# ArachnoProto.net
KiCad netlist of a schematic drawn in EAGLE
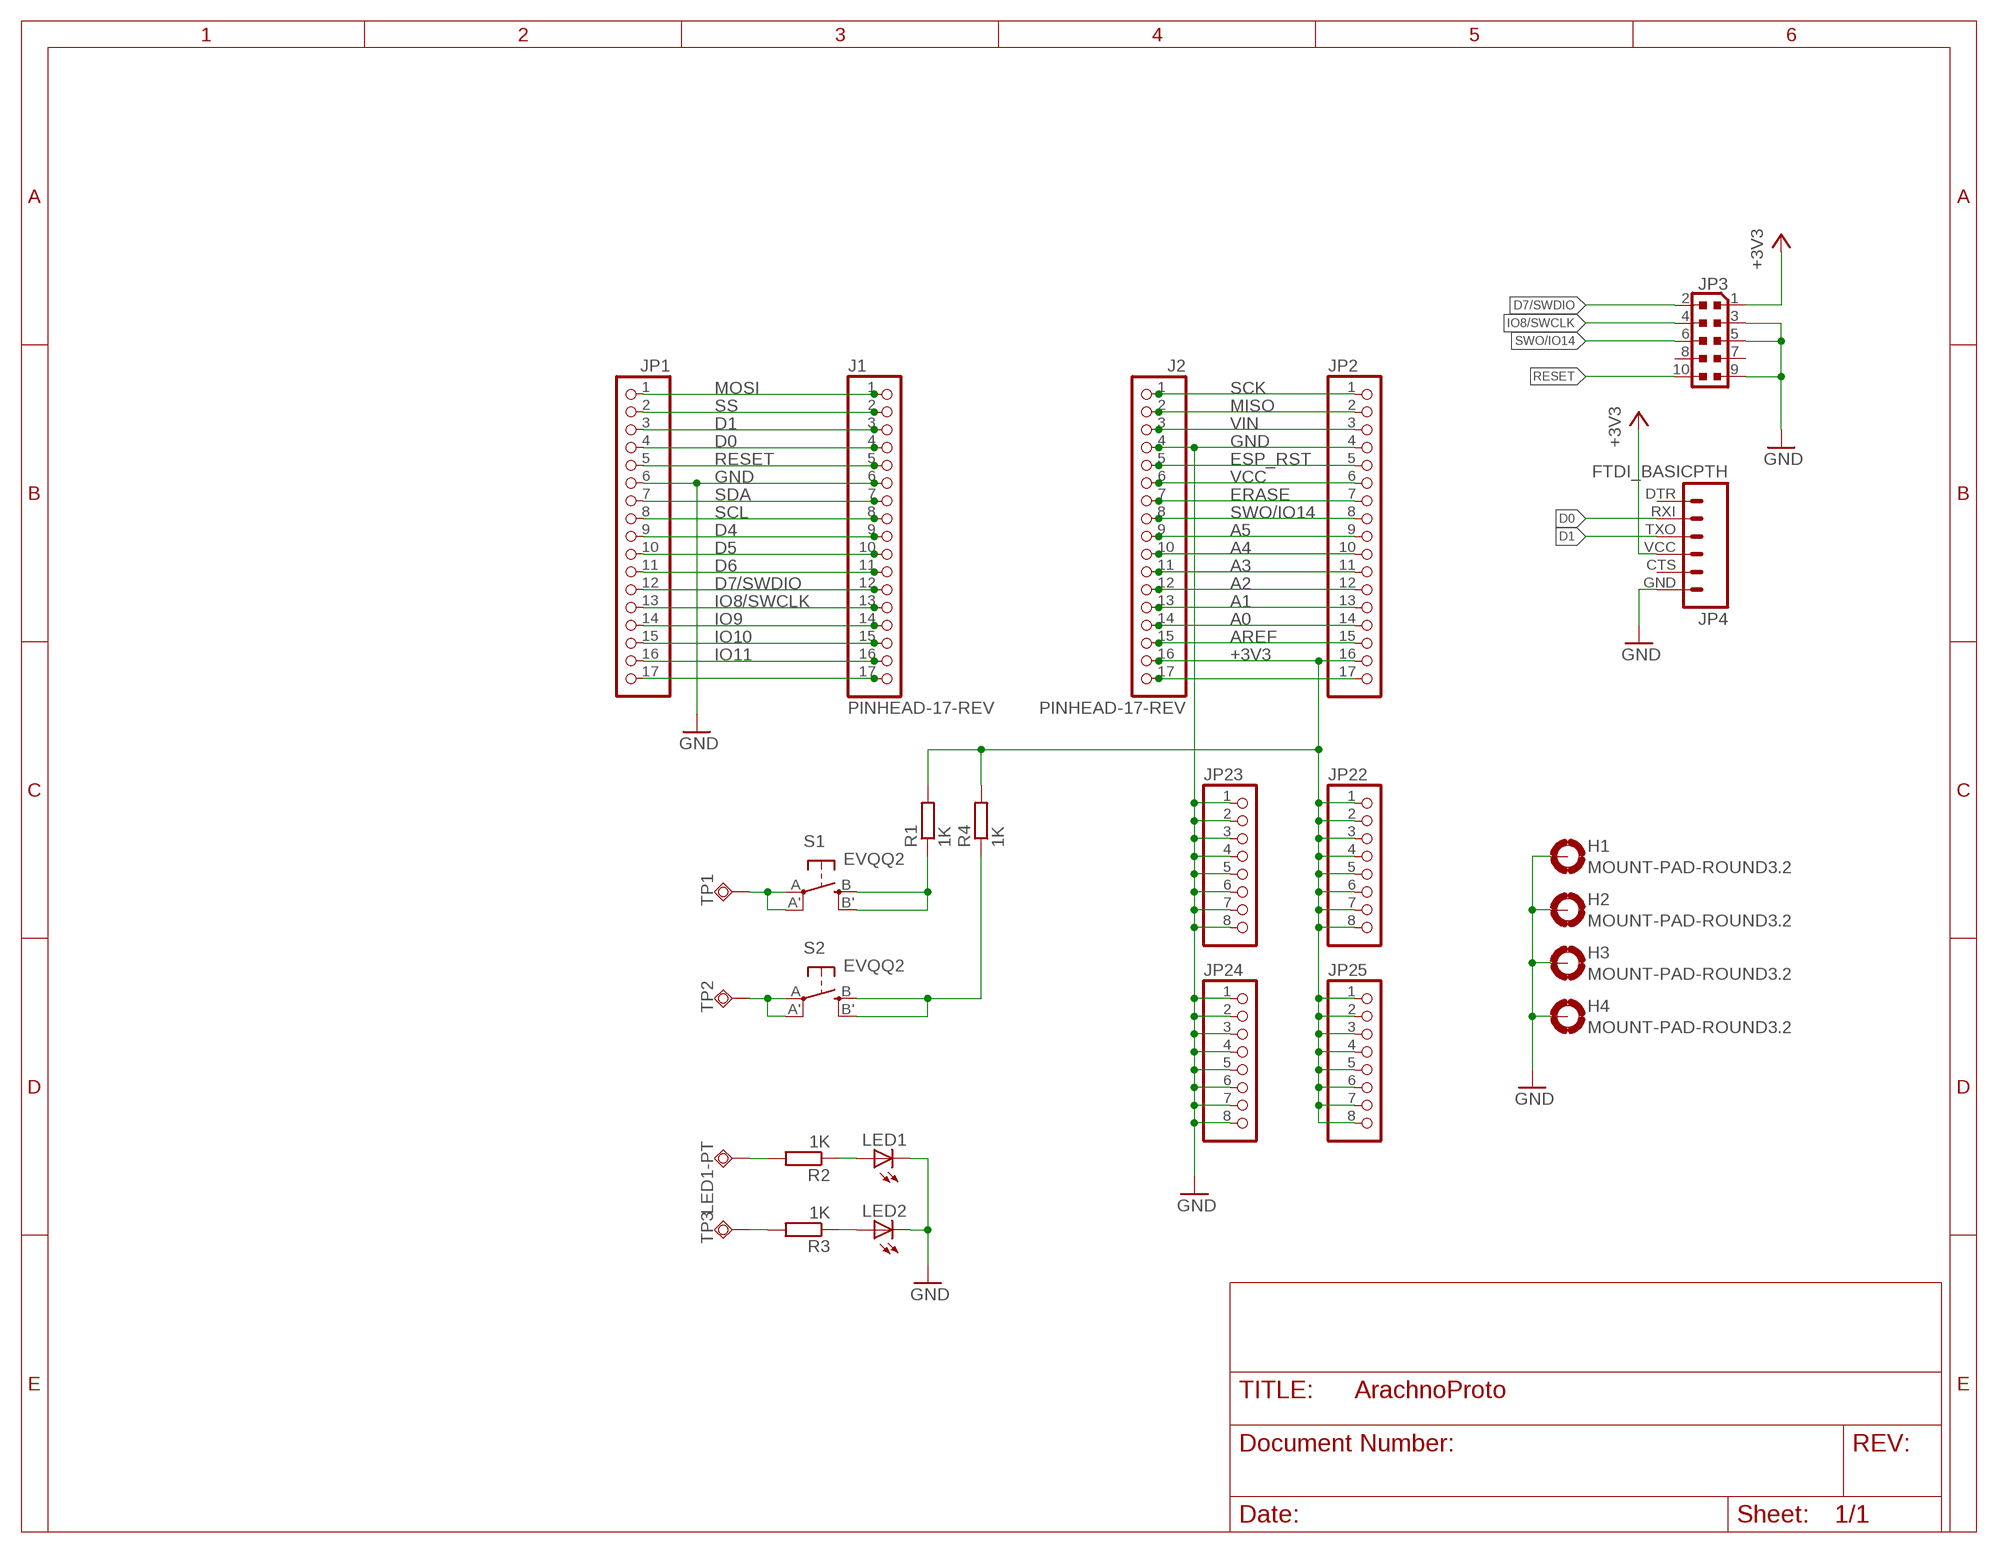
[diagram p0: schematic, sheet 1]

(export (version "E")
  (design (tool "Eeschema 10.0.6"))
  (components
    (comp (ref "H1")
      (value "MOUNT-PAD-ROUND3.2")
      (footprint "eagle-import:3,2-PAD")
      (libsource (lib "eagle-import") (part "MOUNT-PAD-ROUND3.2"))
    )
    (comp (ref "H2")
      (value "MOUNT-PAD-ROUND3.2")
      (footprint "eagle-import:3,2-PAD")
      (libsource (lib "eagle-import") (part "MOUNT-PAD-ROUND3.2"))
    )
    (comp (ref "H3")
      (value "MOUNT-PAD-ROUND3.2")
      (footprint "eagle-import:3,2-PAD")
      (libsource (lib "eagle-import") (part "MOUNT-PAD-ROUND3.2"))
    )
    (comp (ref "H4")
      (value "MOUNT-PAD-ROUND3.2")
      (footprint "eagle-import:3,2-PAD")
      (libsource (lib "eagle-import") (part "MOUNT-PAD-ROUND3.2"))
    )
    (comp (ref "J1")
      (value "PINHEAD-17-REV")
      (footprint "eagle-import:4UCONN-12573")
      (libsource (lib "eagle-import") (part "PINHEAD-17-REV"))
    )
    (comp (ref "J2")
      (value "PINHEAD-17-REV")
      (footprint "eagle-import:4UCONN-12573")
      (libsource (lib "eagle-import") (part "PINHEAD-17-REV"))
    )
    (comp (ref "JP1")
      (value "PINHD-1X17")
      (footprint "eagle-import:1X17")
      (libsource (lib "eagle-import") (part "PINHD-1X17"))
    )
    (comp (ref "JP2")
      (value "PINHD-1X17")
      (footprint "eagle-import:1X17")
      (libsource (lib "eagle-import") (part "PINHD-1X17"))
    )
    (comp (ref "JP3")
      (value "PINHEAD_PINHD-2X5PASSO127")
      (footprint "eagle-import:PINHEAD_2X05_127")
      (libsource (lib "eagle-import") (part "PINHEAD_PINHD-2X5PASSO127"))
    )
    (comp (ref "JP4")
      (value "FTDI_BASICPTH")
      (footprint "eagle-import:FTDI_BASIC")
      (libsource (lib "eagle-import") (part "FTDI_BASICPTH"))
    )
    (comp (ref "JP22")
      (value "PINHD-1X8")
      (footprint "eagle-import:1X08")
      (libsource (lib "eagle-import") (part "PINHD-1X8"))
    )
    (comp (ref "JP23")
      (value "PINHD-1X8")
      (footprint "eagle-import:1X08")
      (libsource (lib "eagle-import") (part "PINHD-1X8"))
    )
    (comp (ref "JP24")
      (value "PINHD-1X8")
      (footprint "eagle-import:1X08")
      (libsource (lib "eagle-import") (part "PINHD-1X8"))
    )
    (comp (ref "JP25")
      (value "PINHD-1X8")
      (footprint "eagle-import:1X08")
      (libsource (lib "eagle-import") (part "PINHD-1X8"))
    )
    (comp (ref "LED1")
      (value "LEDCHIPLED_1206")
      (footprint "eagle-import:CHIPLED_1206")
      (libsource (lib "eagle-import") (part "LEDCHIPLED_1206"))
    )
    (comp (ref "LED1-PT")
      (value "TPSQPAD1-20Y")
      (footprint "eagle-import:P1-20Y")
      (libsource (lib "eagle-import") (part "TPSQPAD1-20Y"))
    )
    (comp (ref "LED2")
      (value "LEDCHIPLED_1206")
      (footprint "eagle-import:CHIPLED_1206")
      (libsource (lib "eagle-import") (part "LEDCHIPLED_1206"))
    )
    (comp (ref "R1")
      (value "1K")
      (footprint "eagle-import:R1206")
      (libsource (lib "eagle-import") (part "R-EU_R1206"))
    )
    (comp (ref "R2")
      (value "1K")
      (footprint "eagle-import:R1206")
      (libsource (lib "eagle-import") (part "R-EU_R1206"))
    )
    (comp (ref "R3")
      (value "1K")
      (footprint "eagle-import:R1206")
      (libsource (lib "eagle-import") (part "R-EU_R1206"))
    )
    (comp (ref "R4")
      (value "1K")
      (footprint "eagle-import:R1206")
      (libsource (lib "eagle-import") (part "R-EU_R1206"))
    )
    (comp (ref "S1")
      (value "EVQQ2")
      (footprint "eagle-import:EVQ-Q2")
      (libsource (lib "eagle-import") (part "EVQQ2"))
    )
    (comp (ref "S2")
      (value "EVQQ2")
      (footprint "eagle-import:EVQ-Q2")
      (libsource (lib "eagle-import") (part "EVQQ2"))
    )
    (comp (ref "TP1")
      (value "TPSQPAD1-20Y")
      (footprint "eagle-import:P1-20Y")
      (libsource (lib "eagle-import") (part "TPSQPAD1-20Y"))
    )
    (comp (ref "TP2")
      (value "TPSQPAD1-20Y")
      (footprint "eagle-import:P1-20Y")
      (libsource (lib "eagle-import") (part "TPSQPAD1-20Y"))
    )
    (comp (ref "TP3")
      (value "TPSQPAD1-20Y")
      (footprint "eagle-import:P1-20Y")
      (libsource (lib "eagle-import") (part "TPSQPAD1-20Y"))
    )
  )
  (nets
    (net (code "1") (name "+3V3") (class "Default")
      (node (ref "J2") (pin "16") (pinfunction "16_16") (pintype "passive"))
      (node (ref "J2") (pin "33") (pinfunction "33_33") (pintype "passive"))
      (node (ref "J2") (pin "50") (pinfunction "50_50") (pintype "passive"))
      (node (ref "JP2") (pin "16") (pinfunction "16_16") (pintype "passive"))
      (node (ref "JP22") (pin "1") (pinfunction "1_1") (pintype "passive"))
      (node (ref "JP22") (pin "2") (pinfunction "2_2") (pintype "passive"))
      (node (ref "JP22") (pin "3") (pinfunction "3_3") (pintype "passive"))
      (node (ref "JP22") (pin "4") (pinfunction "4_4") (pintype "passive"))
      (node (ref "JP22") (pin "5") (pinfunction "5_5") (pintype "passive"))
      (node (ref "JP22") (pin "6") (pinfunction "6_6") (pintype "passive"))
      (node (ref "JP22") (pin "7") (pinfunction "7_7") (pintype "passive"))
      (node (ref "JP22") (pin "8") (pinfunction "8_8") (pintype "passive"))
      (node (ref "JP25") (pin "1") (pinfunction "1_1") (pintype "passive"))
      (node (ref "JP25") (pin "2") (pinfunction "2_2") (pintype "passive"))
      (node (ref "JP25") (pin "3") (pinfunction "3_3") (pintype "passive"))
      (node (ref "JP25") (pin "4") (pinfunction "4_4") (pintype "passive"))
      (node (ref "JP25") (pin "5") (pinfunction "5_5") (pintype "passive"))
      (node (ref "JP25") (pin "6") (pinfunction "6_6") (pintype "passive"))
      (node (ref "JP25") (pin "7") (pinfunction "7_7") (pintype "passive"))
      (node (ref "JP25") (pin "8") (pinfunction "8_8") (pintype "passive"))
      (node (ref "JP3") (pin "1") (pinfunction "1_1") (pintype "passive"))
      (node (ref "JP4") (pin "VCC") (pinfunction "4_VCC") (pintype "passive"))
      (node (ref "R1") (pin "2") (pinfunction "2_2") (pintype "passive"))
      (node (ref "R4") (pin "2") (pinfunction "2_2") (pintype "passive"))
    )
    (net (code "2") (name "/A0") (class "Default")
      (node (ref "J2") (pin "14") (pinfunction "14_14") (pintype "passive"))
      (node (ref "J2") (pin "31") (pinfunction "31_31") (pintype "passive"))
      (node (ref "J2") (pin "48") (pinfunction "48_48") (pintype "passive"))
      (node (ref "JP2") (pin "14") (pinfunction "14_14") (pintype "passive"))
    )
    (net (code "3") (name "/A1") (class "Default")
      (node (ref "J2") (pin "13") (pinfunction "13_13") (pintype "passive"))
      (node (ref "J2") (pin "30") (pinfunction "30_30") (pintype "passive"))
      (node (ref "J2") (pin "47") (pinfunction "47_47") (pintype "passive"))
      (node (ref "JP2") (pin "13") (pinfunction "13_13") (pintype "passive"))
    )
    (net (code "4") (name "/A2") (class "Default")
      (node (ref "J2") (pin "12") (pinfunction "12_12") (pintype "passive"))
      (node (ref "J2") (pin "29") (pinfunction "29_29") (pintype "passive"))
      (node (ref "J2") (pin "46") (pinfunction "46_46") (pintype "passive"))
      (node (ref "JP2") (pin "12") (pinfunction "12_12") (pintype "passive"))
    )
    (net (code "5") (name "/A3") (class "Default")
      (node (ref "J2") (pin "11") (pinfunction "11_11") (pintype "passive"))
      (node (ref "J2") (pin "28") (pinfunction "28_28") (pintype "passive"))
      (node (ref "J2") (pin "45") (pinfunction "45_45") (pintype "passive"))
      (node (ref "JP2") (pin "11") (pinfunction "11_11") (pintype "passive"))
    )
    (net (code "6") (name "/A4") (class "Default")
      (node (ref "J2") (pin "10") (pinfunction "10_10") (pintype "passive"))
      (node (ref "J2") (pin "27") (pinfunction "27_27") (pintype "passive"))
      (node (ref "J2") (pin "44") (pinfunction "44_44") (pintype "passive"))
      (node (ref "JP2") (pin "10") (pinfunction "10_10") (pintype "passive"))
    )
    (net (code "7") (name "/A5") (class "Default")
      (node (ref "J2") (pin "26") (pinfunction "26_26") (pintype "passive"))
      (node (ref "J2") (pin "43") (pinfunction "43_43") (pintype "passive"))
      (node (ref "J2") (pin "9") (pinfunction "9_9") (pintype "passive"))
      (node (ref "JP2") (pin "9") (pinfunction "9_9") (pintype "passive"))
    )
    (net (code "8") (name "/AREF") (class "Default")
      (node (ref "J2") (pin "15") (pinfunction "15_15") (pintype "passive"))
      (node (ref "J2") (pin "32") (pinfunction "32_32") (pintype "passive"))
      (node (ref "J2") (pin "49") (pinfunction "49_49") (pintype "passive"))
      (node (ref "JP2") (pin "15") (pinfunction "15_15") (pintype "passive"))
    )
    (net (code "9") (name "/D4") (class "Default")
      (node (ref "J1") (pin "26") (pinfunction "26_26") (pintype "passive"))
      (node (ref "J1") (pin "43") (pinfunction "43_43") (pintype "passive"))
      (node (ref "J1") (pin "9") (pinfunction "9_9") (pintype "passive"))
      (node (ref "JP1") (pin "9") (pinfunction "9_9") (pintype "passive"))
    )
    (net (code "10") (name "/D5") (class "Default")
      (node (ref "J1") (pin "10") (pinfunction "10_10") (pintype "passive"))
      (node (ref "J1") (pin "27") (pinfunction "27_27") (pintype "passive"))
      (node (ref "J1") (pin "44") (pinfunction "44_44") (pintype "passive"))
      (node (ref "JP1") (pin "10") (pinfunction "10_10") (pintype "passive"))
    )
    (net (code "11") (name "/D6") (class "Default")
      (node (ref "J1") (pin "11") (pinfunction "11_11") (pintype "passive"))
      (node (ref "J1") (pin "28") (pinfunction "28_28") (pintype "passive"))
      (node (ref "J1") (pin "45") (pinfunction "45_45") (pintype "passive"))
      (node (ref "JP1") (pin "11") (pinfunction "11_11") (pintype "passive"))
    )
    (net (code "12") (name "/ERASE") (class "Default")
      (node (ref "J2") (pin "24") (pinfunction "24_24") (pintype "passive"))
      (node (ref "J2") (pin "41") (pinfunction "41_41") (pintype "passive"))
      (node (ref "J2") (pin "7") (pinfunction "7_7") (pintype "passive"))
      (node (ref "JP2") (pin "7") (pinfunction "7_7") (pintype "passive"))
    )
    (net (code "13") (name "/ESP_RST") (class "Default")
      (node (ref "J2") (pin "22") (pinfunction "22_22") (pintype "passive"))
      (node (ref "J2") (pin "39") (pinfunction "39_39") (pintype "passive"))
      (node (ref "J2") (pin "5") (pinfunction "5_5") (pintype "passive"))
      (node (ref "JP2") (pin "5") (pinfunction "5_5") (pintype "passive"))
    )
    (net (code "14") (name "/IO9") (class "Default")
      (node (ref "J1") (pin "14") (pinfunction "14_14") (pintype "passive"))
      (node (ref "J1") (pin "31") (pinfunction "31_31") (pintype "passive"))
      (node (ref "J1") (pin "48") (pinfunction "48_48") (pintype "passive"))
      (node (ref "JP1") (pin "14") (pinfunction "14_14") (pintype "passive"))
    )
    (net (code "15") (name "/IO10") (class "Default")
      (node (ref "J1") (pin "15") (pinfunction "15_15") (pintype "passive"))
      (node (ref "J1") (pin "32") (pinfunction "32_32") (pintype "passive"))
      (node (ref "J1") (pin "49") (pinfunction "49_49") (pintype "passive"))
      (node (ref "JP1") (pin "15") (pinfunction "15_15") (pintype "passive"))
    )
    (net (code "16") (name "/IO11") (class "Default")
      (node (ref "J1") (pin "16") (pinfunction "16_16") (pintype "passive"))
      (node (ref "J1") (pin "33") (pinfunction "33_33") (pintype "passive"))
      (node (ref "J1") (pin "50") (pinfunction "50_50") (pintype "passive"))
      (node (ref "JP1") (pin "16") (pinfunction "16_16") (pintype "passive"))
    )
    (net (code "17") (name "/MISO") (class "Default")
      (node (ref "J2") (pin "19") (pinfunction "19_19") (pintype "passive"))
      (node (ref "J2") (pin "2") (pinfunction "2_2") (pintype "passive"))
      (node (ref "J2") (pin "36") (pinfunction "36_36") (pintype "passive"))
      (node (ref "JP2") (pin "2") (pinfunction "2_2") (pintype "passive"))
    )
    (net (code "18") (name "/MOSI") (class "Default")
      (node (ref "J1") (pin "1") (pinfunction "1_1") (pintype "passive"))
      (node (ref "J1") (pin "18") (pinfunction "18_18") (pintype "passive"))
      (node (ref "J1") (pin "35") (pinfunction "35_35") (pintype "passive"))
      (node (ref "JP1") (pin "1") (pinfunction "1_1") (pintype "passive"))
    )
    (net (code "19") (name "/SCK") (class "Default")
      (node (ref "J2") (pin "1") (pinfunction "1_1") (pintype "passive"))
      (node (ref "J2") (pin "18") (pinfunction "18_18") (pintype "passive"))
      (node (ref "J2") (pin "35") (pinfunction "35_35") (pintype "passive"))
      (node (ref "JP2") (pin "1") (pinfunction "1_1") (pintype "passive"))
    )
    (net (code "20") (name "/SCL") (class "Default")
      (node (ref "J1") (pin "25") (pinfunction "25_25") (pintype "passive"))
      (node (ref "J1") (pin "42") (pinfunction "42_42") (pintype "passive"))
      (node (ref "J1") (pin "8") (pinfunction "8_8") (pintype "passive"))
      (node (ref "JP1") (pin "8") (pinfunction "8_8") (pintype "passive"))
    )
    (net (code "21") (name "/SDA") (class "Default")
      (node (ref "J1") (pin "24") (pinfunction "24_24") (pintype "passive"))
      (node (ref "J1") (pin "41") (pinfunction "41_41") (pintype "passive"))
      (node (ref "J1") (pin "7") (pinfunction "7_7") (pintype "passive"))
      (node (ref "JP1") (pin "7") (pinfunction "7_7") (pintype "passive"))
    )
    (net (code "22") (name "/SS") (class "Default")
      (node (ref "J1") (pin "19") (pinfunction "19_19") (pintype "passive"))
      (node (ref "J1") (pin "2") (pinfunction "2_2") (pintype "passive"))
      (node (ref "J1") (pin "36") (pinfunction "36_36") (pintype "passive"))
      (node (ref "JP1") (pin "2") (pinfunction "2_2") (pintype "passive"))
    )
    (net (code "23") (name "/VCC") (class "Default")
      (node (ref "J2") (pin "23") (pinfunction "23_23") (pintype "passive"))
      (node (ref "J2") (pin "40") (pinfunction "40_40") (pintype "passive"))
      (node (ref "J2") (pin "6") (pinfunction "6_6") (pintype "passive"))
      (node (ref "JP2") (pin "6") (pinfunction "6_6") (pintype "passive"))
    )
    (net (code "24") (name "/VIN") (class "Default")
      (node (ref "J2") (pin "20") (pinfunction "20_20") (pintype "passive"))
      (node (ref "J2") (pin "3") (pinfunction "3_3") (pintype "passive"))
      (node (ref "J2") (pin "37") (pinfunction "37_37") (pintype "passive"))
      (node (ref "JP2") (pin "3") (pinfunction "3_3") (pintype "passive"))
    )
    (net (code "25") (name "D0") (class "Default")
      (node (ref "J1") (pin "21") (pinfunction "21_21") (pintype "passive"))
      (node (ref "J1") (pin "38") (pinfunction "38_38") (pintype "passive"))
      (node (ref "J1") (pin "4") (pinfunction "4_4") (pintype "passive"))
      (node (ref "JP1") (pin "4") (pinfunction "4_4") (pintype "passive"))
      (node (ref "JP4") (pin "RXI") (pinfunction "2_RXI") (pintype "passive"))
    )
    (net (code "26") (name "D1") (class "Default")
      (node (ref "J1") (pin "20") (pinfunction "20_20") (pintype "passive"))
      (node (ref "J1") (pin "3") (pinfunction "3_3") (pintype "passive"))
      (node (ref "J1") (pin "37") (pinfunction "37_37") (pintype "passive"))
      (node (ref "JP1") (pin "3") (pinfunction "3_3") (pintype "passive"))
      (node (ref "JP4") (pin "TXO") (pinfunction "3_TXO") (pintype "passive"))
    )
    (net (code "27") (name "D7{slash}SWDIO") (class "Default")
      (node (ref "J1") (pin "12") (pinfunction "12_12") (pintype "passive"))
      (node (ref "J1") (pin "29") (pinfunction "29_29") (pintype "passive"))
      (node (ref "J1") (pin "46") (pinfunction "46_46") (pintype "passive"))
      (node (ref "JP1") (pin "12") (pinfunction "12_12") (pintype "passive"))
      (node (ref "JP3") (pin "2") (pinfunction "2_2") (pintype "passive"))
    )
    (net (code "28") (name "GND") (class "Default")
      (node (ref "H1") (pin "B3,2") (pinfunction "MOUNT_B3,2") (pintype "passive"))
      (node (ref "H2") (pin "B3,2") (pinfunction "MOUNT_B3,2") (pintype "passive"))
      (node (ref "H3") (pin "B3,2") (pinfunction "MOUNT_B3,2") (pintype "passive"))
      (node (ref "H4") (pin "B3,2") (pinfunction "MOUNT_B3,2") (pintype "passive"))
      (node (ref "J1") (pin "23") (pinfunction "23_23") (pintype "passive"))
      (node (ref "J1") (pin "40") (pinfunction "40_40") (pintype "passive"))
      (node (ref "J1") (pin "6") (pinfunction "6_6") (pintype "passive"))
      (node (ref "J2") (pin "21") (pinfunction "21_21") (pintype "passive"))
      (node (ref "J2") (pin "38") (pinfunction "38_38") (pintype "passive"))
      (node (ref "J2") (pin "4") (pinfunction "4_4") (pintype "passive"))
      (node (ref "JP1") (pin "6") (pinfunction "6_6") (pintype "passive"))
      (node (ref "JP2") (pin "4") (pinfunction "4_4") (pintype "passive"))
      (node (ref "JP23") (pin "1") (pinfunction "1_1") (pintype "passive"))
      (node (ref "JP23") (pin "2") (pinfunction "2_2") (pintype "passive"))
      (node (ref "JP23") (pin "3") (pinfunction "3_3") (pintype "passive"))
      (node (ref "JP23") (pin "4") (pinfunction "4_4") (pintype "passive"))
      (node (ref "JP23") (pin "5") (pinfunction "5_5") (pintype "passive"))
      (node (ref "JP23") (pin "6") (pinfunction "6_6") (pintype "passive"))
      (node (ref "JP23") (pin "7") (pinfunction "7_7") (pintype "passive"))
      (node (ref "JP23") (pin "8") (pinfunction "8_8") (pintype "passive"))
      (node (ref "JP24") (pin "1") (pinfunction "1_1") (pintype "passive"))
      (node (ref "JP24") (pin "2") (pinfunction "2_2") (pintype "passive"))
      (node (ref "JP24") (pin "3") (pinfunction "3_3") (pintype "passive"))
      (node (ref "JP24") (pin "4") (pinfunction "4_4") (pintype "passive"))
      (node (ref "JP24") (pin "5") (pinfunction "5_5") (pintype "passive"))
      (node (ref "JP24") (pin "6") (pinfunction "6_6") (pintype "passive"))
      (node (ref "JP24") (pin "7") (pinfunction "7_7") (pintype "passive"))
      (node (ref "JP24") (pin "8") (pinfunction "8_8") (pintype "passive"))
      (node (ref "JP3") (pin "3") (pinfunction "3_3") (pintype "passive"))
      (node (ref "JP3") (pin "5") (pinfunction "5_5") (pintype "passive"))
      (node (ref "JP3") (pin "9") (pinfunction "9_9") (pintype "passive"))
      (node (ref "JP4") (pin "GND") (pinfunction "6_GND") (pintype "passive"))
      (node (ref "LED1") (pin "C") (pinfunction "C_C") (pintype "passive"))
      (node (ref "LED2") (pin "C") (pinfunction "C_C") (pintype "passive"))
    )
    (net (code "29") (name "IO8{slash}SWCLK") (class "Default")
      (node (ref "J1") (pin "13") (pinfunction "13_13") (pintype "passive"))
      (node (ref "J1") (pin "30") (pinfunction "30_30") (pintype "passive"))
      (node (ref "J1") (pin "47") (pinfunction "47_47") (pintype "passive"))
      (node (ref "JP1") (pin "13") (pinfunction "13_13") (pintype "passive"))
      (node (ref "JP3") (pin "4") (pinfunction "4_4") (pintype "passive"))
    )
    (net (code "30") (name "Net-(J1-Pad17)") (class "Default")
      (node (ref "J1") (pin "17") (pinfunction "17_17") (pintype "passive"))
      (node (ref "J1") (pin "34") (pinfunction "34_34") (pintype "passive"))
      (node (ref "J1") (pin "51") (pinfunction "51_51") (pintype "passive"))
      (node (ref "JP1") (pin "17") (pinfunction "17_17") (pintype "passive"))
    )
    (net (code "31") (name "Net-(J2-Pad17)") (class "Default")
      (node (ref "J2") (pin "17") (pinfunction "17_17") (pintype "passive"))
      (node (ref "J2") (pin "34") (pinfunction "34_34") (pintype "passive"))
      (node (ref "J2") (pin "51") (pinfunction "51_51") (pintype "passive"))
      (node (ref "JP2") (pin "17") (pinfunction "17_17") (pintype "passive"))
    )
    (net (code "32") (name "Net-(LED1-PT-PadTP)") (class "Default")
      (node (ref "LED1-PT") (pin "TP") (pinfunction "TP_TP") (pintype "input"))
      (node (ref "R2") (pin "2") (pinfunction "2_2") (pintype "passive"))
    )
    (net (code "33") (name "Net-(LED1-PadA)") (class "Default")
      (node (ref "LED1") (pin "A") (pinfunction "A_A") (pintype "passive"))
      (node (ref "R2") (pin "1") (pinfunction "1_1") (pintype "passive"))
    )
    (net (code "34") (name "Net-(LED2-PadA)") (class "Default")
      (node (ref "LED2") (pin "A") (pinfunction "A_A") (pintype "passive"))
      (node (ref "R3") (pin "1") (pinfunction "1_1") (pintype "passive"))
    )
    (net (code "35") (name "Net-(R3-Pad2)") (class "Default")
      (node (ref "R3") (pin "2") (pinfunction "2_2") (pintype "passive"))
      (node (ref "TP3") (pin "TP") (pinfunction "TP_TP") (pintype "input"))
    )
    (net (code "36") (name "Net-(S1-P)") (class "Default")
      (node (ref "S1") (pin "A") (pinfunction "P_A") (pintype "passive"))
      (node (ref "S1") (pin "A'") (pinfunction "P1_A'") (pintype "passive"))
      (node (ref "TP1") (pin "TP") (pinfunction "TP_TP") (pintype "input"))
    )
    (net (code "37") (name "Net-(S1-S)") (class "Default")
      (node (ref "R1") (pin "1") (pinfunction "1_1") (pintype "passive"))
      (node (ref "S1") (pin "B") (pinfunction "S_B") (pintype "passive"))
      (node (ref "S1") (pin "B'") (pinfunction "S1_B'") (pintype "passive"))
    )
    (net (code "38") (name "Net-(S2-P)") (class "Default")
      (node (ref "S2") (pin "A") (pinfunction "P_A") (pintype "passive"))
      (node (ref "S2") (pin "A'") (pinfunction "P1_A'") (pintype "passive"))
      (node (ref "TP2") (pin "TP") (pinfunction "TP_TP") (pintype "input"))
    )
    (net (code "39") (name "Net-(S2-S)") (class "Default")
      (node (ref "R4") (pin "1") (pinfunction "1_1") (pintype "passive"))
      (node (ref "S2") (pin "B") (pinfunction "S_B") (pintype "passive"))
      (node (ref "S2") (pin "B'") (pinfunction "S1_B'") (pintype "passive"))
    )
    (net (code "40") (name "RESET") (class "Default")
      (node (ref "J1") (pin "22") (pinfunction "22_22") (pintype "passive"))
      (node (ref "J1") (pin "39") (pinfunction "39_39") (pintype "passive"))
      (node (ref "J1") (pin "5") (pinfunction "5_5") (pintype "passive"))
      (node (ref "JP1") (pin "5") (pinfunction "5_5") (pintype "passive"))
      (node (ref "JP3") (pin "10") (pinfunction "10_10") (pintype "passive"))
    )
    (net (code "41") (name "SWO{slash}IO14") (class "Default")
      (node (ref "J2") (pin "25") (pinfunction "25_25") (pintype "passive"))
      (node (ref "J2") (pin "42") (pinfunction "42_42") (pintype "passive"))
      (node (ref "J2") (pin "8") (pinfunction "8_8") (pintype "passive"))
      (node (ref "JP2") (pin "8") (pinfunction "8_8") (pintype "passive"))
      (node (ref "JP3") (pin "6") (pinfunction "6_6") (pintype "passive"))
    )
    (net (code "42") (name "unconnected-(JP3-Pad7)") (class "Default")
      (node (ref "JP3") (pin "7") (pinfunction "7_7") (pintype "passive"))
    )
    (net (code "43") (name "unconnected-(JP3-Pad8)") (class "Default")
      (node (ref "JP3") (pin "8") (pinfunction "8_8") (pintype "passive"))
    )
    (net (code "44") (name "unconnected-(JP4-1-PadDTR)") (class "Default")
      (node (ref "JP4") (pin "DTR") (pinfunction "1_DTR") (pintype "passive"))
    )
    (net (code "45") (name "unconnected-(JP4-5-PadCTS)") (class "Default")
      (node (ref "JP4") (pin "CTS") (pinfunction "5_CTS") (pintype "passive"))
    )
  )
)
